# Fri3D_2020_Peripherals.net
KiCad netlist of a schematic drawn in Altium Designer
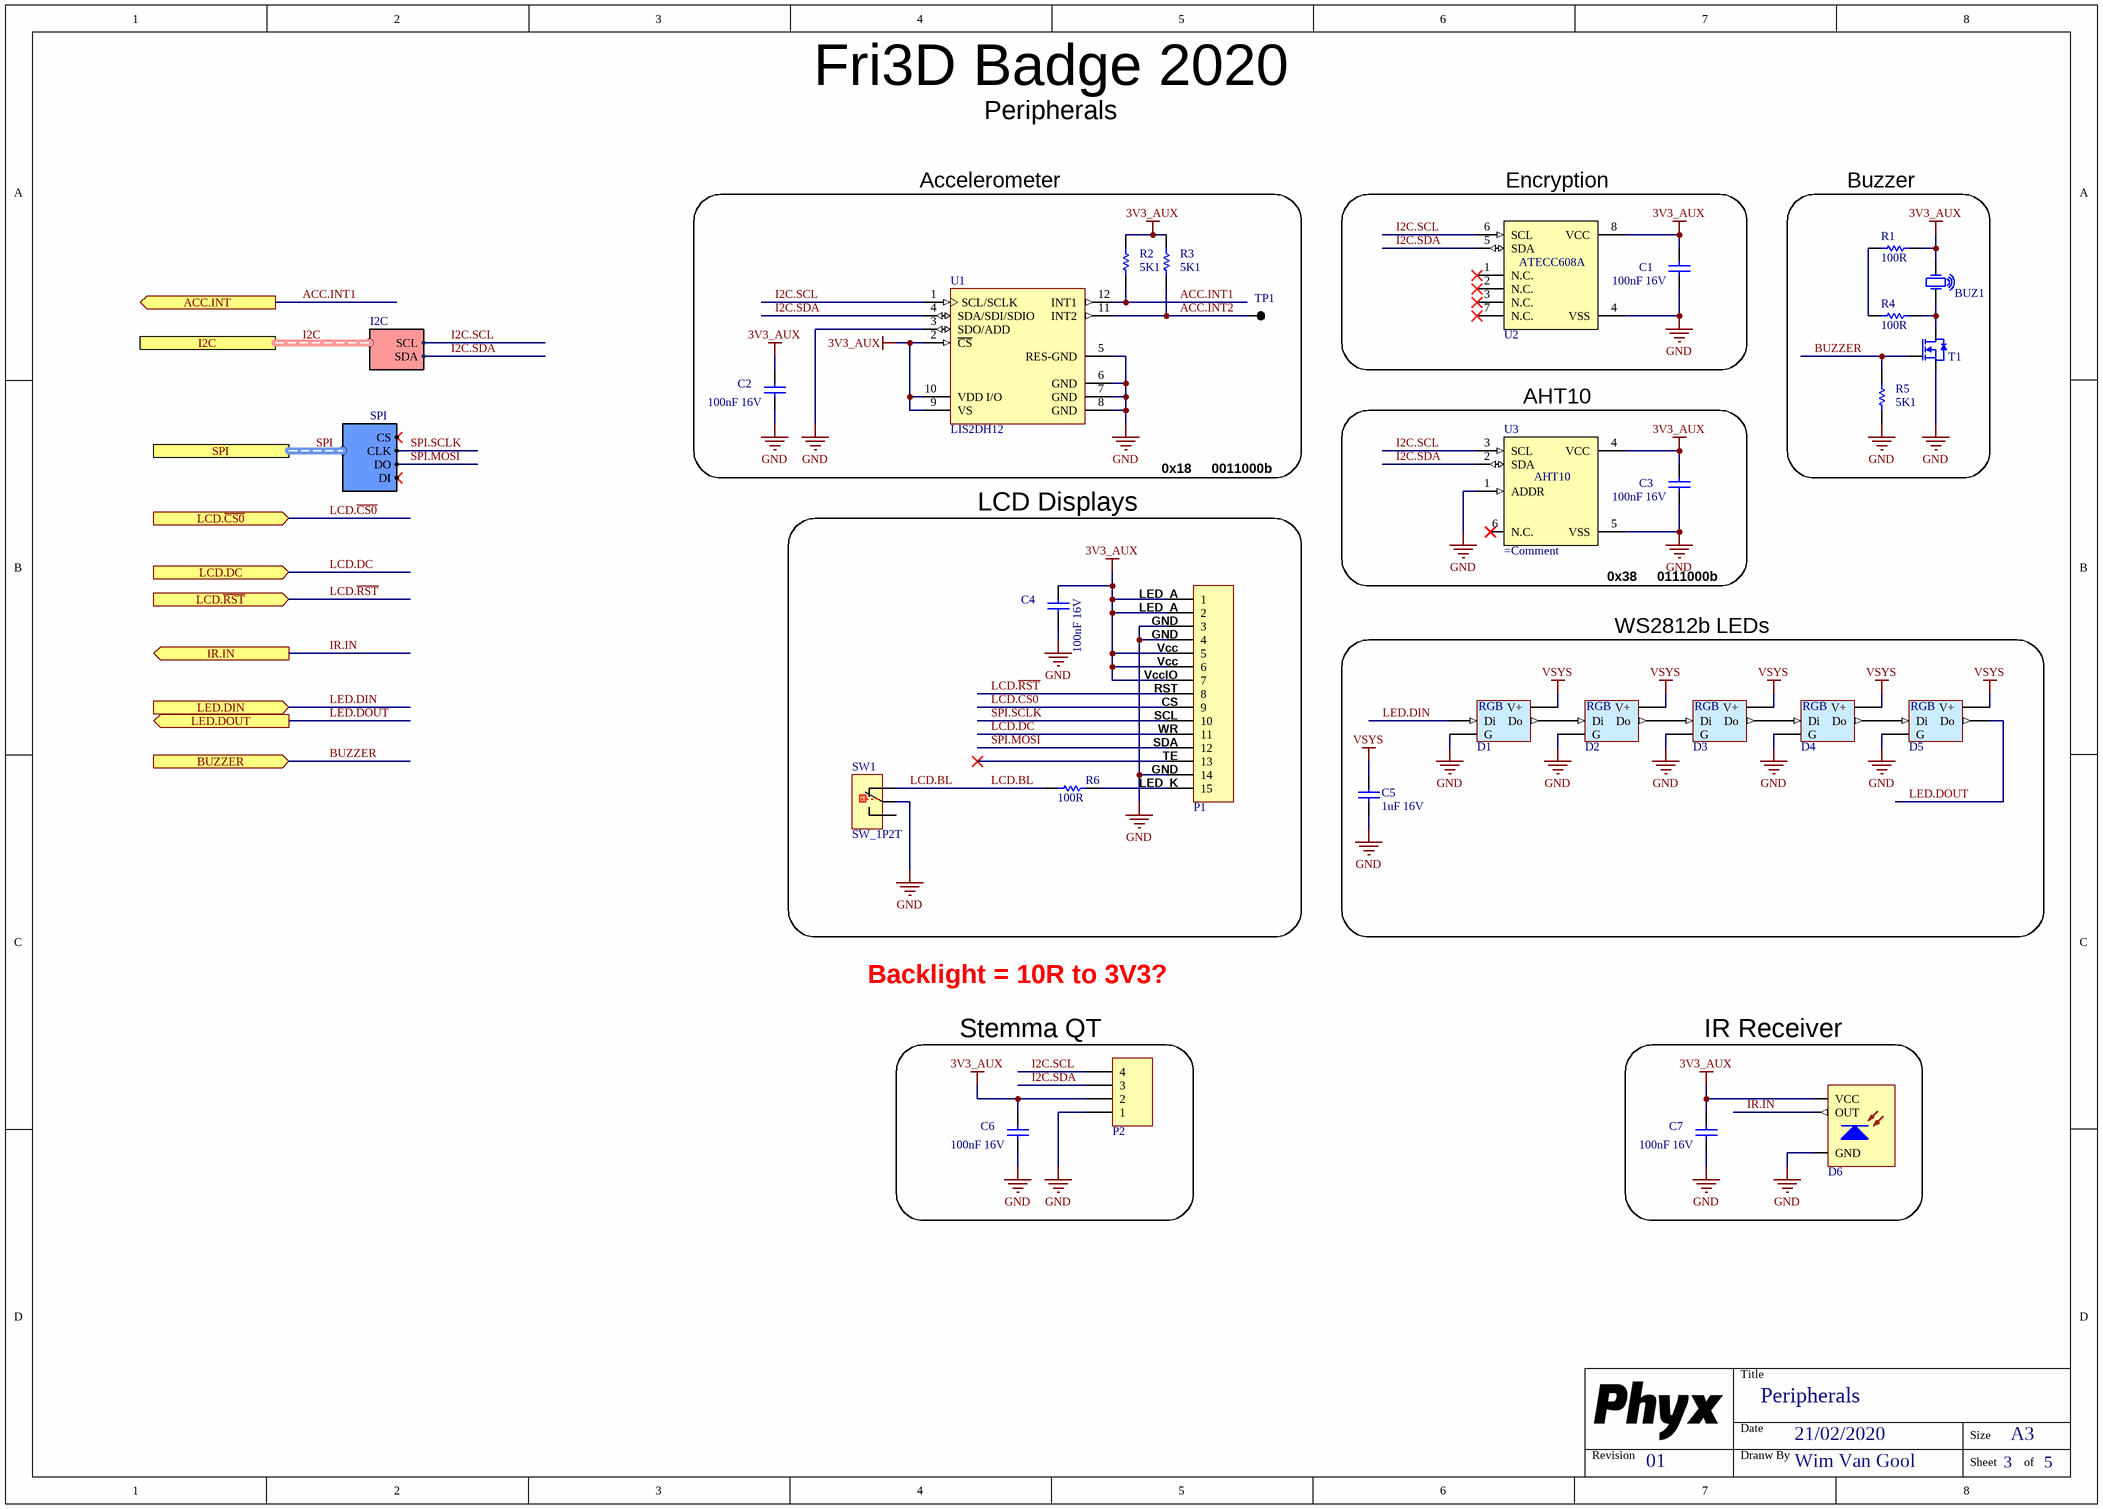
[diagram p0: Fri3D_2020_Peripherals.SchDoc]

(export (version "E")
  (design (tool "Eeschema 10.0.6"))
  (components
    (comp (ref "BUZ1")
      (value "12x12x3mm Piezo Buzzer Transducer 81dB")
      (footprint "CUI_CMT-1203-SMT")
      (description "Crystal Oscillator")
      (libsource (lib "Phyx_Components") (part "Buzzer"))
    )
    (comp (ref "C1")
      (value "100nF 16V")
      (footprint "C0603_N")
      (description "Capacitor Ceramic")
      (libsource (lib "Phyx_Components") (part "CAP_CERAMIC"))
    )
    (comp (ref "C2")
      (value "100nF 16V")
      (footprint "C0603_N")
      (description "Capacitor Ceramic")
      (libsource (lib "Phyx_Components") (part "CAP_CERAMIC"))
    )
    (comp (ref "C3")
      (value "100nF 16V")
      (footprint "C0603_N")
      (description "Capacitor Ceramic")
      (libsource (lib "Phyx_Components") (part "CAP_CERAMIC"))
    )
    (comp (ref "C4")
      (value "100nF 16V")
      (footprint "C0603_N")
      (description "Capacitor Ceramic")
      (libsource (lib "Phyx_Components") (part "CAP_CERAMIC"))
    )
    (comp (ref "C5")
      (value "1uF 16V")
      (footprint "C0603_N")
      (description "Capacitor Ceramic")
      (fields (field (name "Comment") "CAP_CERAMIC"))
      (libsource (lib "Phyx_Components") (part "CAP_CERAMIC"))
    )
    (comp (ref "C6")
      (value "100nF 16V")
      (footprint "C0603_N")
      (description "Capacitor Ceramic")
      (libsource (lib "Phyx_Components") (part "CAP_CERAMIC"))
    )
    (comp (ref "C7")
      (value "100nF 16V")
      (footprint "C0603_N")
      (description "Capacitor Ceramic")
      (libsource (lib "Phyx_Components") (part "CAP_CERAMIC"))
    )
    (comp (ref "D1")
      (value "WS2812 based digital RGB LED 5050 Black package")
      (footprint "LED_5050_WS2812B_BLACK")
      (description "=Description")
      (libsource (lib "Phyx_Components") (part "LED_RGB_WS2812B_5050"))
    )
    (comp (ref "D2")
      (value "WS2812 based digital RGB LED 5050 Black package")
      (footprint "LED_5050_WS2812B_BLACK")
      (description "=Description")
      (libsource (lib "Phyx_Components") (part "LED_RGB_WS2812B_5050"))
    )
    (comp (ref "D3")
      (value "WS2812 based digital RGB LED 5050 Black package")
      (footprint "LED_5050_WS2812B_BLACK")
      (description "=Description")
      (libsource (lib "Phyx_Components") (part "LED_RGB_WS2812B_5050"))
    )
    (comp (ref "D4")
      (value "WS2812 based digital RGB LED 5050 Black package")
      (footprint "LED_5050_WS2812B_BLACK")
      (description "=Description")
      (libsource (lib "Phyx_Components") (part "LED_RGB_WS2812B_5050"))
    )
    (comp (ref "D5")
      (value "WS2812 based digital RGB LED 5050 Black package")
      (footprint "LED_5050_WS2812B_BLACK")
      (description "=Description")
      (libsource (lib "Phyx_Components") (part "LED_RGB_WS2812B_5050"))
    )
    (comp (ref "D6")
      (value "IRM-3638N3F14 Infrared Receiver 38 kHz 45° 2.7-5.5V")
      (footprint "VIS_TSOP381x_BENT")
      (description "=Description")
      (libsource (lib "Phyx_Components") (part "PHO_IR_TSOP381x"))
    )
    (comp (ref "P1")
      (value "Bottom contact FPC 0.3mm pitch 15 contacts")
      (footprint "FPC_AFE03-S15FMA-1H")
      (libsource (lib "Phyx_Components") (part "Header 15"))
    )
    (comp (ref "P2")
      (value "Header 1.0mm RA Shrouded 4")
      (footprint "WE_665104131822")
      (libsource (lib "Phyx_Components") (part "Header 4"))
    )
    (comp (ref "R1")
      (value "100R")
      (footprint "R0603_N")
      (fields (field (name "Comment") "RESISTOR"))
      (libsource (lib "Phyx_Components") (part "RESISTOR"))
    )
    (comp (ref "R2")
      (value "5K1")
      (footprint "R0603_N")
      (fields (field (name "Comment") "RESISTOR"))
      (libsource (lib "Phyx_Components") (part "RESISTOR"))
    )
    (comp (ref "R3")
      (value "5K1")
      (footprint "R0603_N")
      (fields (field (name "Comment") "RESISTOR"))
      (libsource (lib "Phyx_Components") (part "RESISTOR"))
    )
    (comp (ref "R4")
      (value "100R")
      (footprint "R0603_N")
      (fields (field (name "Comment") "RESISTOR"))
      (libsource (lib "Phyx_Components") (part "RESISTOR"))
    )
    (comp (ref "R5")
      (value "5K1")
      (footprint "R0603_N")
      (fields (field (name "Comment") "RESISTOR"))
      (libsource (lib "Phyx_Components") (part "RESISTOR"))
    )
    (comp (ref "R6")
      (value "100R")
      (footprint "R0603_N")
      (fields (field (name "Comment") "RESISTOR"))
      (libsource (lib "Phyx_Components") (part "RESISTOR"))
    )
    (comp (ref "SW1")
      (value "SW_1P2T")
      (footprint "WE_450404015514")
      (libsource (lib "Phyx_Components") (part "SW_1P2T"))
    )
    (comp (ref "T1")
      (value "0.2A N-Ch MOSFET Vgs 3.2")
      (footprint "SOT23-3")
      (libsource (lib "Phyx_Components") (part "N_MOSFET_GSD"))
    )
    (comp (ref "TP1")
      (value "TEST_PAD")
      (footprint "TP_0.8mm")
      (libsource (lib "Phyx_Components") (part "TEST_PAD"))
    )
    (comp (ref "U1")
      (value "LIS2DH12")
      (footprint "STM_LGA12_2x2")
      (description "=Description")
      (libsource (lib "Phyx_Components") (part "STM_LIS2DH12"))
    )
    (comp (ref "U2")
      (value "Encryption Authentication with 72b SN, SHA-256, AES-128")
      (footprint "SOIC_N_8")
      (description "=Description")
      (libsource (lib "Phyx_Components") (part "ATECC608A-SSHDA"))
    )
    (comp (ref "U3")
      (value "~")
      (footprint "AHT10")
      (description "=Description")
      (libsource (lib "Phyx_Components") (part "AHT10"))
    )
  )
  (nets
    (net (code "3") (name "/ACC.INT1") (class "Default")
      (node (ref "R2") (pin "2") (pinfunction "2_2") (pintype "passive"))
      (node (ref "U1") (pin "12") (pinfunction "INT1_12") (pintype "output"))
    )
    (net (code "4") (name "/ACC.INT2") (class "Default")
      (node (ref "R3") (pin "2") (pinfunction "2_2") (pintype "passive"))
      (node (ref "TP1") (pin "1") (pinfunction "1_1") (pintype "passive"))
      (node (ref "U1") (pin "11") (pinfunction "INT2_11") (pintype "output"))
    )
    (net (code "5") (name "/BUZZER") (class "Default")
      (node (ref "R5") (pin "1") (pinfunction "1_1") (pintype "passive"))
      (node (ref "T1") (pin "1") (pinfunction "G_1") (pintype "passive"))
    )
    (net (code "6") (name "/I2C.SCL") (class "Default")
      (node (ref "P2") (pin "4") (pinfunction "4_4") (pintype "passive"))
      (node (ref "U1") (pin "1") (pinfunction "SCL/SCLK_1") (pintype "input"))
      (node (ref "U2") (pin "6") (pinfunction "SCL_6") (pintype "input"))
      (node (ref "U3") (pin "3") (pinfunction "SCL_3") (pintype "input"))
    )
    (net (code "7") (name "/I2C.SDA") (class "Default")
      (node (ref "P2") (pin "3") (pinfunction "3_3") (pintype "passive"))
      (node (ref "U1") (pin "4") (pinfunction "SDA/SDI/SDIO_4") (pintype "bidirectional"))
      (node (ref "U2") (pin "5") (pinfunction "SDA_5") (pintype "bidirectional"))
      (node (ref "U3") (pin "2") (pinfunction "SDA_2") (pintype "bidirectional"))
    )
    (net (code "9") (name "/IR.IN") (class "Default")
      (node (ref "D6") (pin "1") (pinfunction "OUT_1") (pintype "output"))
    )
    (net (code "10") (name "/LCD.BL") (class "Default")
      (node (ref "R6") (pin "2") (pinfunction "2_2") (pintype "passive"))
      (node (ref "SW1") (pin "1") (pinfunction "1_1") (pintype "passive"))
    )
    (net (code "11") (name "/LCD.DC") (class "Default")
      (node (ref "P1") (pin "11") (pinfunction "11_11") (pintype "passive"))
    )
    (net (code "12") (name "/LCD.~{CS0}") (class "Default")
      (node (ref "P1") (pin "9") (pinfunction "9_9") (pintype "passive"))
    )
    (net (code "13") (name "/LCD.~{RST}") (class "Default")
      (node (ref "P1") (pin "8") (pinfunction "8_8") (pintype "passive"))
    )
    (net (code "14") (name "/LED.DIN") (class "Default")
      (node (ref "D1") (pin "4") (pinfunction "Di_4") (pintype "input"))
    )
    (net (code "15") (name "/LED.DOUT") (class "Default")
      (node (ref "D5") (pin "2") (pinfunction "Do_2") (pintype "output"))
    )
    (net (code "16") (name "/SPI.MOSI") (class "Default")
      (node (ref "P1") (pin "12") (pinfunction "12_12") (pintype "passive"))
    )
    (net (code "17") (name "/SPI.SCLK") (class "Default")
      (node (ref "P1") (pin "10") (pinfunction "10_10") (pintype "passive"))
    )
    (net (code "19") (name "3V3_AUX") (class "Default")
      (node (ref "BUZ1") (pin "1") (pinfunction "OSC1_1") (pintype "passive"))
      (node (ref "C1") (pin "1") (pinfunction "1_1") (pintype "passive"))
      (node (ref "C2") (pin "1") (pinfunction "1_1") (pintype "passive"))
      (node (ref "C3") (pin "1") (pinfunction "1_1") (pintype "passive"))
      (node (ref "C4") (pin "1") (pinfunction "1_1") (pintype "passive"))
      (node (ref "C6") (pin "1") (pinfunction "1_1") (pintype "passive"))
      (node (ref "C7") (pin "1") (pinfunction "1_1") (pintype "passive"))
      (node (ref "D6") (pin "3") (pinfunction "VCC_3") (pintype "power_in"))
      (node (ref "P1") (pin "1") (pinfunction "1_1") (pintype "passive"))
      (node (ref "P1") (pin "2") (pinfunction "2_2") (pintype "passive"))
      (node (ref "P1") (pin "5") (pinfunction "5_5") (pintype "passive"))
      (node (ref "P1") (pin "6") (pinfunction "6_6") (pintype "passive"))
      (node (ref "P1") (pin "7") (pinfunction "7_7") (pintype "passive"))
      (node (ref "P2") (pin "2") (pinfunction "2_2") (pintype "passive"))
      (node (ref "R1") (pin "1") (pinfunction "1_1") (pintype "passive"))
      (node (ref "R2") (pin "1") (pinfunction "1_1") (pintype "passive"))
      (node (ref "R3") (pin "1") (pinfunction "1_1") (pintype "passive"))
      (node (ref "U1") (pin "10") (pinfunction "VDD_I/O_10") (pintype "power_in"))
      (node (ref "U1") (pin "2") (pinfunction "~{CS}_2") (pintype "input"))
      (node (ref "U1") (pin "9") (pinfunction "VS_9") (pintype "power_in"))
      (node (ref "U2") (pin "8") (pinfunction "VCC_8") (pintype "power_in"))
      (node (ref "U3") (pin "4") (pinfunction "VCC_4") (pintype "power_in"))
    )
    (net (code "20") (name "GND") (class "Default")
      (node (ref "C1") (pin "2") (pinfunction "2_2") (pintype "passive"))
      (node (ref "C2") (pin "2") (pinfunction "2_2") (pintype "passive"))
      (node (ref "C3") (pin "2") (pinfunction "2_2") (pintype "passive"))
      (node (ref "C4") (pin "2") (pinfunction "2_2") (pintype "passive"))
      (node (ref "C5") (pin "2") (pinfunction "2_2") (pintype "passive"))
      (node (ref "C6") (pin "2") (pinfunction "2_2") (pintype "passive"))
      (node (ref "C7") (pin "2") (pinfunction "2_2") (pintype "passive"))
      (node (ref "D1") (pin "3") (pinfunction "G_3") (pintype "power_in"))
      (node (ref "D2") (pin "3") (pinfunction "G_3") (pintype "power_in"))
      (node (ref "D3") (pin "3") (pinfunction "G_3") (pintype "power_in"))
      (node (ref "D4") (pin "3") (pinfunction "G_3") (pintype "power_in"))
      (node (ref "D5") (pin "3") (pinfunction "G_3") (pintype "power_in"))
      (node (ref "D6") (pin "2") (pinfunction "GND_2") (pintype "power_in"))
      (node (ref "P1") (pin "14") (pinfunction "14_14") (pintype "passive"))
      (node (ref "P1") (pin "3") (pinfunction "3_3") (pintype "passive"))
      (node (ref "P1") (pin "4") (pinfunction "4_4") (pintype "passive"))
      (node (ref "P2") (pin "1") (pinfunction "1_1") (pintype "passive"))
      (node (ref "R5") (pin "2") (pinfunction "2_2") (pintype "passive"))
      (node (ref "SW1") (pin "2") (pinfunction "2_2") (pintype "passive"))
      (node (ref "T1") (pin "2") (pinfunction "S_2") (pintype "passive"))
      (node (ref "U1") (pin "3") (pinfunction "SDO/ADD_3") (pintype "bidirectional"))
      (node (ref "U1") (pin "5") (pinfunction "RES-GND_5") (pintype "passive"))
      (node (ref "U1") (pin "6") (pinfunction "GND_6") (pintype "power_in"))
      (node (ref "U1") (pin "7") (pinfunction "GND_7") (pintype "power_in"))
      (node (ref "U1") (pin "8") (pinfunction "GND_8") (pintype "power_in"))
      (node (ref "U2") (pin "4") (pinfunction "VSS_4") (pintype "power_in"))
      (node (ref "U3") (pin "1") (pinfunction "ADDR_1") (pintype "input"))
      (node (ref "U3") (pin "5") (pinfunction "VSS_5") (pintype "power_in"))
    )
    (net (code "21") (name "Net-(BUZ1-OSC2)") (class "Default")
      (node (ref "BUZ1") (pin "2") (pinfunction "OSC2_2") (pintype "passive"))
      (node (ref "R4") (pin "1") (pinfunction "1_1") (pintype "passive"))
      (node (ref "T1") (pin "3") (pinfunction "D_3") (pintype "passive"))
    )
    (net (code "22") (name "Net-(D1-Do)") (class "Default")
      (node (ref "D1") (pin "2") (pinfunction "Do_2") (pintype "output"))
      (node (ref "D2") (pin "4") (pinfunction "Di_4") (pintype "input"))
    )
    (net (code "23") (name "Net-(D2-Do)") (class "Default")
      (node (ref "D2") (pin "2") (pinfunction "Do_2") (pintype "output"))
      (node (ref "D3") (pin "4") (pinfunction "Di_4") (pintype "input"))
    )
    (net (code "24") (name "Net-(D3-Do)") (class "Default")
      (node (ref "D3") (pin "2") (pinfunction "Do_2") (pintype "output"))
      (node (ref "D4") (pin "4") (pinfunction "Di_4") (pintype "input"))
    )
    (net (code "25") (name "Net-(D4-Do)") (class "Default")
      (node (ref "D4") (pin "2") (pinfunction "Do_2") (pintype "output"))
      (node (ref "D5") (pin "4") (pinfunction "Di_4") (pintype "input"))
    )
    (net (code "26") (name "Net-(P1-Pad15)") (class "Default")
      (node (ref "P1") (pin "15") (pinfunction "15_15") (pintype "passive"))
      (node (ref "R6") (pin "1") (pinfunction "1_1") (pintype "passive"))
    )
    (net (code "27") (name "Net-(R1-Pad2)") (class "Default")
      (node (ref "R1") (pin "2") (pinfunction "2_2") (pintype "passive"))
      (node (ref "R4") (pin "2") (pinfunction "2_2") (pintype "passive"))
    )
    (net (code "28") (name "VSYS") (class "Default")
      (node (ref "C5") (pin "1") (pinfunction "1_1") (pintype "passive"))
      (node (ref "D1") (pin "1") (pinfunction "V+_1") (pintype "power_in"))
      (node (ref "D2") (pin "1") (pinfunction "V+_1") (pintype "power_in"))
      (node (ref "D3") (pin "1") (pinfunction "V+_1") (pintype "power_in"))
      (node (ref "D4") (pin "1") (pinfunction "V+_1") (pintype "power_in"))
      (node (ref "D5") (pin "1") (pinfunction "V+_1") (pintype "power_in"))
    )
    (net (code "29") (name "unconnected-(P1-Pad13)") (class "Default")
      (node (ref "P1") (pin "13") (pinfunction "13_13") (pintype "passive+no_connect"))
    )
    (net (code "30") (name "unconnected-(SW1-Pad3)") (class "Default")
      (node (ref "SW1") (pin "3") (pinfunction "3_3") (pintype "passive"))
    )
    (net (code "31") (name "unconnected-(U2-N.C.-Pad1)") (class "Default")
      (node (ref "U2") (pin "1") (pinfunction "N.C._1") (pintype "passive+no_connect"))
    )
    (net (code "32") (name "unconnected-(U2-N.C.-Pad2)") (class "Default")
      (node (ref "U2") (pin "2") (pinfunction "N.C._2") (pintype "passive+no_connect"))
    )
    (net (code "33") (name "unconnected-(U2-N.C.-Pad3)") (class "Default")
      (node (ref "U2") (pin "3") (pinfunction "N.C._3") (pintype "passive+no_connect"))
    )
    (net (code "34") (name "unconnected-(U2-N.C.-Pad7)") (class "Default")
      (node (ref "U2") (pin "7") (pinfunction "N.C._7") (pintype "passive+no_connect"))
    )
    (net (code "35") (name "unconnected-(U3-N.C.-Pad6)") (class "Default")
      (node (ref "U3") (pin "6") (pinfunction "N.C._6") (pintype "passive+no_connect"))
    )
  )
)
